# 7segments.net
KiCad netlist of a schematic drawn in Altium Designer
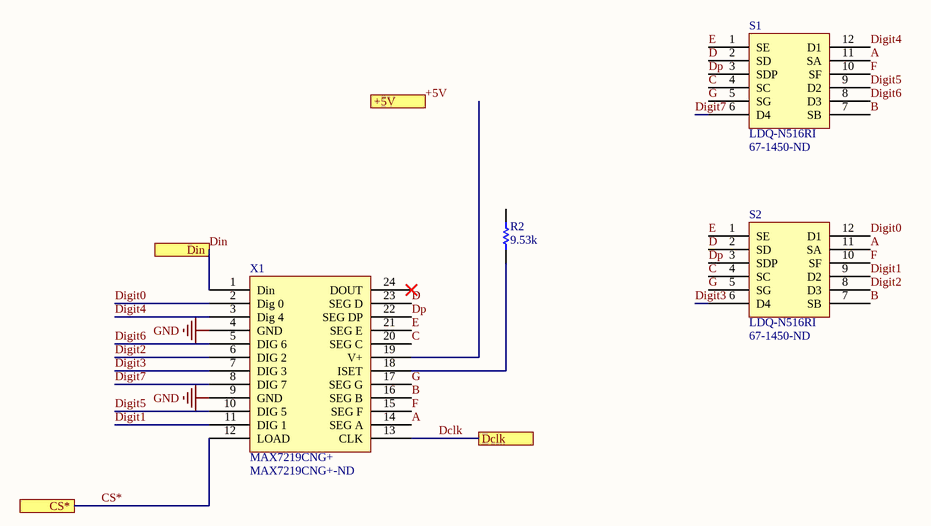
[diagram p0: 7segments.SchDoc]

(export (version "E")
  (design (tool "Eeschema 10.0.6"))
  (components
    (comp (ref "R2")
      (value "9.53k")
      (footprint "Resistor Through Hole")
      (description "MFR-25FBF52-9K53")
      (libsource (lib "ServoInterface") (part "Resistor_9.53k"))
    )
    (comp (ref "S1")
      (value "LDQ-N516RI")
      (footprint "LDQ-516RI")
      (description "LED 7-SEG .56 QUAD S-RED CC MULT")
      (fields (field (name "SUPPLIER PART NUMBER 1") "67-1450-ND"))
      (libsource (lib "ServoInterface") (part "SevenSegment"))
    )
    (comp (ref "S2")
      (value "LDQ-N516RI")
      (footprint "LDQ-516RI")
      (description "LED 7-SEG .56 QUAD S-RED CC MULT")
      (fields (field (name "SUPPLIER PART NUMBER 1") "67-1450-ND"))
      (libsource (lib "ServoInterface") (part "SevenSegment"))
    )
    (comp (ref "X1")
      (value "MAX7219CNG+")
      (footprint "MAX7219")
      (description "Serially Interfaced, 8-Digit LED Display Driver")
      (fields (field (name "SUPPLIER PART NUMBER 1") "MAX7219CNG+-ND"))
      (libsource (lib "ServoInterface") (part "MAX7219"))
    )
  )
  (nets
    (net (code "2") (name "/A") (class "Default")
      (node (ref "S1") (pin "11") (pinfunction "SA_11") (pintype "passive"))
      (node (ref "S2") (pin "11") (pinfunction "SA_11") (pintype "passive"))
      (node (ref "X1") (pin "14") (pinfunction "SEG_A_14") (pintype "passive"))
    )
    (net (code "3") (name "/B") (class "Default")
      (node (ref "S1") (pin "7") (pinfunction "SB_7") (pintype "passive"))
      (node (ref "S2") (pin "7") (pinfunction "SB_7") (pintype "passive"))
      (node (ref "X1") (pin "16") (pinfunction "SEG_B_16") (pintype "passive"))
    )
    (net (code "4") (name "/C") (class "Default")
      (node (ref "S1") (pin "4") (pinfunction "SC_4") (pintype "passive"))
      (node (ref "S2") (pin "4") (pinfunction "SC_4") (pintype "passive"))
      (node (ref "X1") (pin "20") (pinfunction "SEG_C_20") (pintype "passive"))
    )
    (net (code "5") (name "/CS*") (class "Default")
      (node (ref "X1") (pin "12") (pinfunction "LOAD_12") (pintype "passive"))
    )
    (net (code "6") (name "/D") (class "Default")
      (node (ref "S1") (pin "2") (pinfunction "SD_2") (pintype "passive"))
      (node (ref "S2") (pin "2") (pinfunction "SD_2") (pintype "passive"))
      (node (ref "X1") (pin "23") (pinfunction "SEG_D_23") (pintype "passive"))
    )
    (net (code "7") (name "/Dclk") (class "Default")
      (node (ref "X1") (pin "13") (pinfunction "CLK_13") (pintype "passive"))
    )
    (net (code "8") (name "/Digit0") (class "Default")
      (node (ref "S2") (pin "12") (pinfunction "D1_12") (pintype "passive"))
      (node (ref "X1") (pin "2") (pinfunction "Dig_0_2") (pintype "passive"))
    )
    (net (code "9") (name "/Digit1") (class "Default")
      (node (ref "S2") (pin "9") (pinfunction "D2_9") (pintype "passive"))
      (node (ref "X1") (pin "11") (pinfunction "DIG_1_11") (pintype "passive"))
    )
    (net (code "10") (name "/Digit2") (class "Default")
      (node (ref "S2") (pin "8") (pinfunction "D3_8") (pintype "passive"))
      (node (ref "X1") (pin "6") (pinfunction "DIG_2_6") (pintype "passive"))
    )
    (net (code "11") (name "/Digit3") (class "Default")
      (node (ref "S2") (pin "6") (pinfunction "D4_6") (pintype "passive"))
      (node (ref "X1") (pin "7") (pinfunction "DIG_3_7") (pintype "passive"))
    )
    (net (code "12") (name "/Digit4") (class "Default")
      (node (ref "S1") (pin "12") (pinfunction "D1_12") (pintype "passive"))
      (node (ref "X1") (pin "3") (pinfunction "Dig_4_3") (pintype "passive"))
    )
    (net (code "13") (name "/Digit5") (class "Default")
      (node (ref "S1") (pin "9") (pinfunction "D2_9") (pintype "passive"))
      (node (ref "X1") (pin "10") (pinfunction "DIG_5_10") (pintype "passive"))
    )
    (net (code "14") (name "/Digit6") (class "Default")
      (node (ref "S1") (pin "8") (pinfunction "D3_8") (pintype "passive"))
      (node (ref "X1") (pin "5") (pinfunction "DIG_6_5") (pintype "passive"))
    )
    (net (code "15") (name "/Digit7") (class "Default")
      (node (ref "S1") (pin "6") (pinfunction "D4_6") (pintype "passive"))
      (node (ref "X1") (pin "8") (pinfunction "DIG_7_8") (pintype "passive"))
    )
    (net (code "16") (name "/Din") (class "Default")
      (node (ref "X1") (pin "1") (pinfunction "Din_1") (pintype "passive"))
    )
    (net (code "17") (name "/Dp") (class "Default")
      (node (ref "S1") (pin "3") (pinfunction "SDP_3") (pintype "passive"))
      (node (ref "S2") (pin "3") (pinfunction "SDP_3") (pintype "passive"))
      (node (ref "X1") (pin "22") (pinfunction "SEG_DP_22") (pintype "passive"))
    )
    (net (code "18") (name "/E") (class "Default")
      (node (ref "S1") (pin "1") (pinfunction "SE_1") (pintype "passive"))
      (node (ref "S2") (pin "1") (pinfunction "SE_1") (pintype "passive"))
      (node (ref "X1") (pin "21") (pinfunction "SEG_E_21") (pintype "passive"))
    )
    (net (code "19") (name "/F") (class "Default")
      (node (ref "S1") (pin "10") (pinfunction "SF_10") (pintype "passive"))
      (node (ref "S2") (pin "10") (pinfunction "SF_10") (pintype "passive"))
      (node (ref "X1") (pin "15") (pinfunction "SEG_F_15") (pintype "passive"))
    )
    (net (code "20") (name "/G") (class "Default")
      (node (ref "S1") (pin "5") (pinfunction "SG_5") (pintype "passive"))
      (node (ref "S2") (pin "5") (pinfunction "SG_5") (pintype "passive"))
      (node (ref "X1") (pin "17") (pinfunction "SEG_G_17") (pintype "passive"))
    )
    (net (code "21") (name "GND") (class "Default")
      (node (ref "X1") (pin "4") (pinfunction "GND_4") (pintype "passive"))
      (node (ref "X1") (pin "9") (pinfunction "GND_9") (pintype "passive"))
    )
    (net (code "22") (name "Net-(X1-ISET)") (class "Default")
      (node (ref "R2") (pin "1") (pinfunction "1_1") (pintype "passive"))
      (node (ref "X1") (pin "18") (pinfunction "ISET_18") (pintype "passive"))
    )
    (net (code "23") (name "unconnected-(R2-Pad2)") (class "Default")
      (node (ref "R2") (pin "2") (pinfunction "2_2") (pintype "passive"))
    )
    (net (code "24") (name "unconnected-(X1-DOUT-Pad24)") (class "Default")
      (node (ref "X1") (pin "24") (pinfunction "DOUT_24") (pintype "passive+no_connect"))
    )
    (net (code "25") (name "unconnected-(X1-V+-Pad19)") (class "Default")
      (node (ref "X1") (pin "19") (pinfunction "V+_19") (pintype "passive"))
    )
  )
)
